# Sheet1.net
KiCad netlist of a schematic drawn in Altium Designer
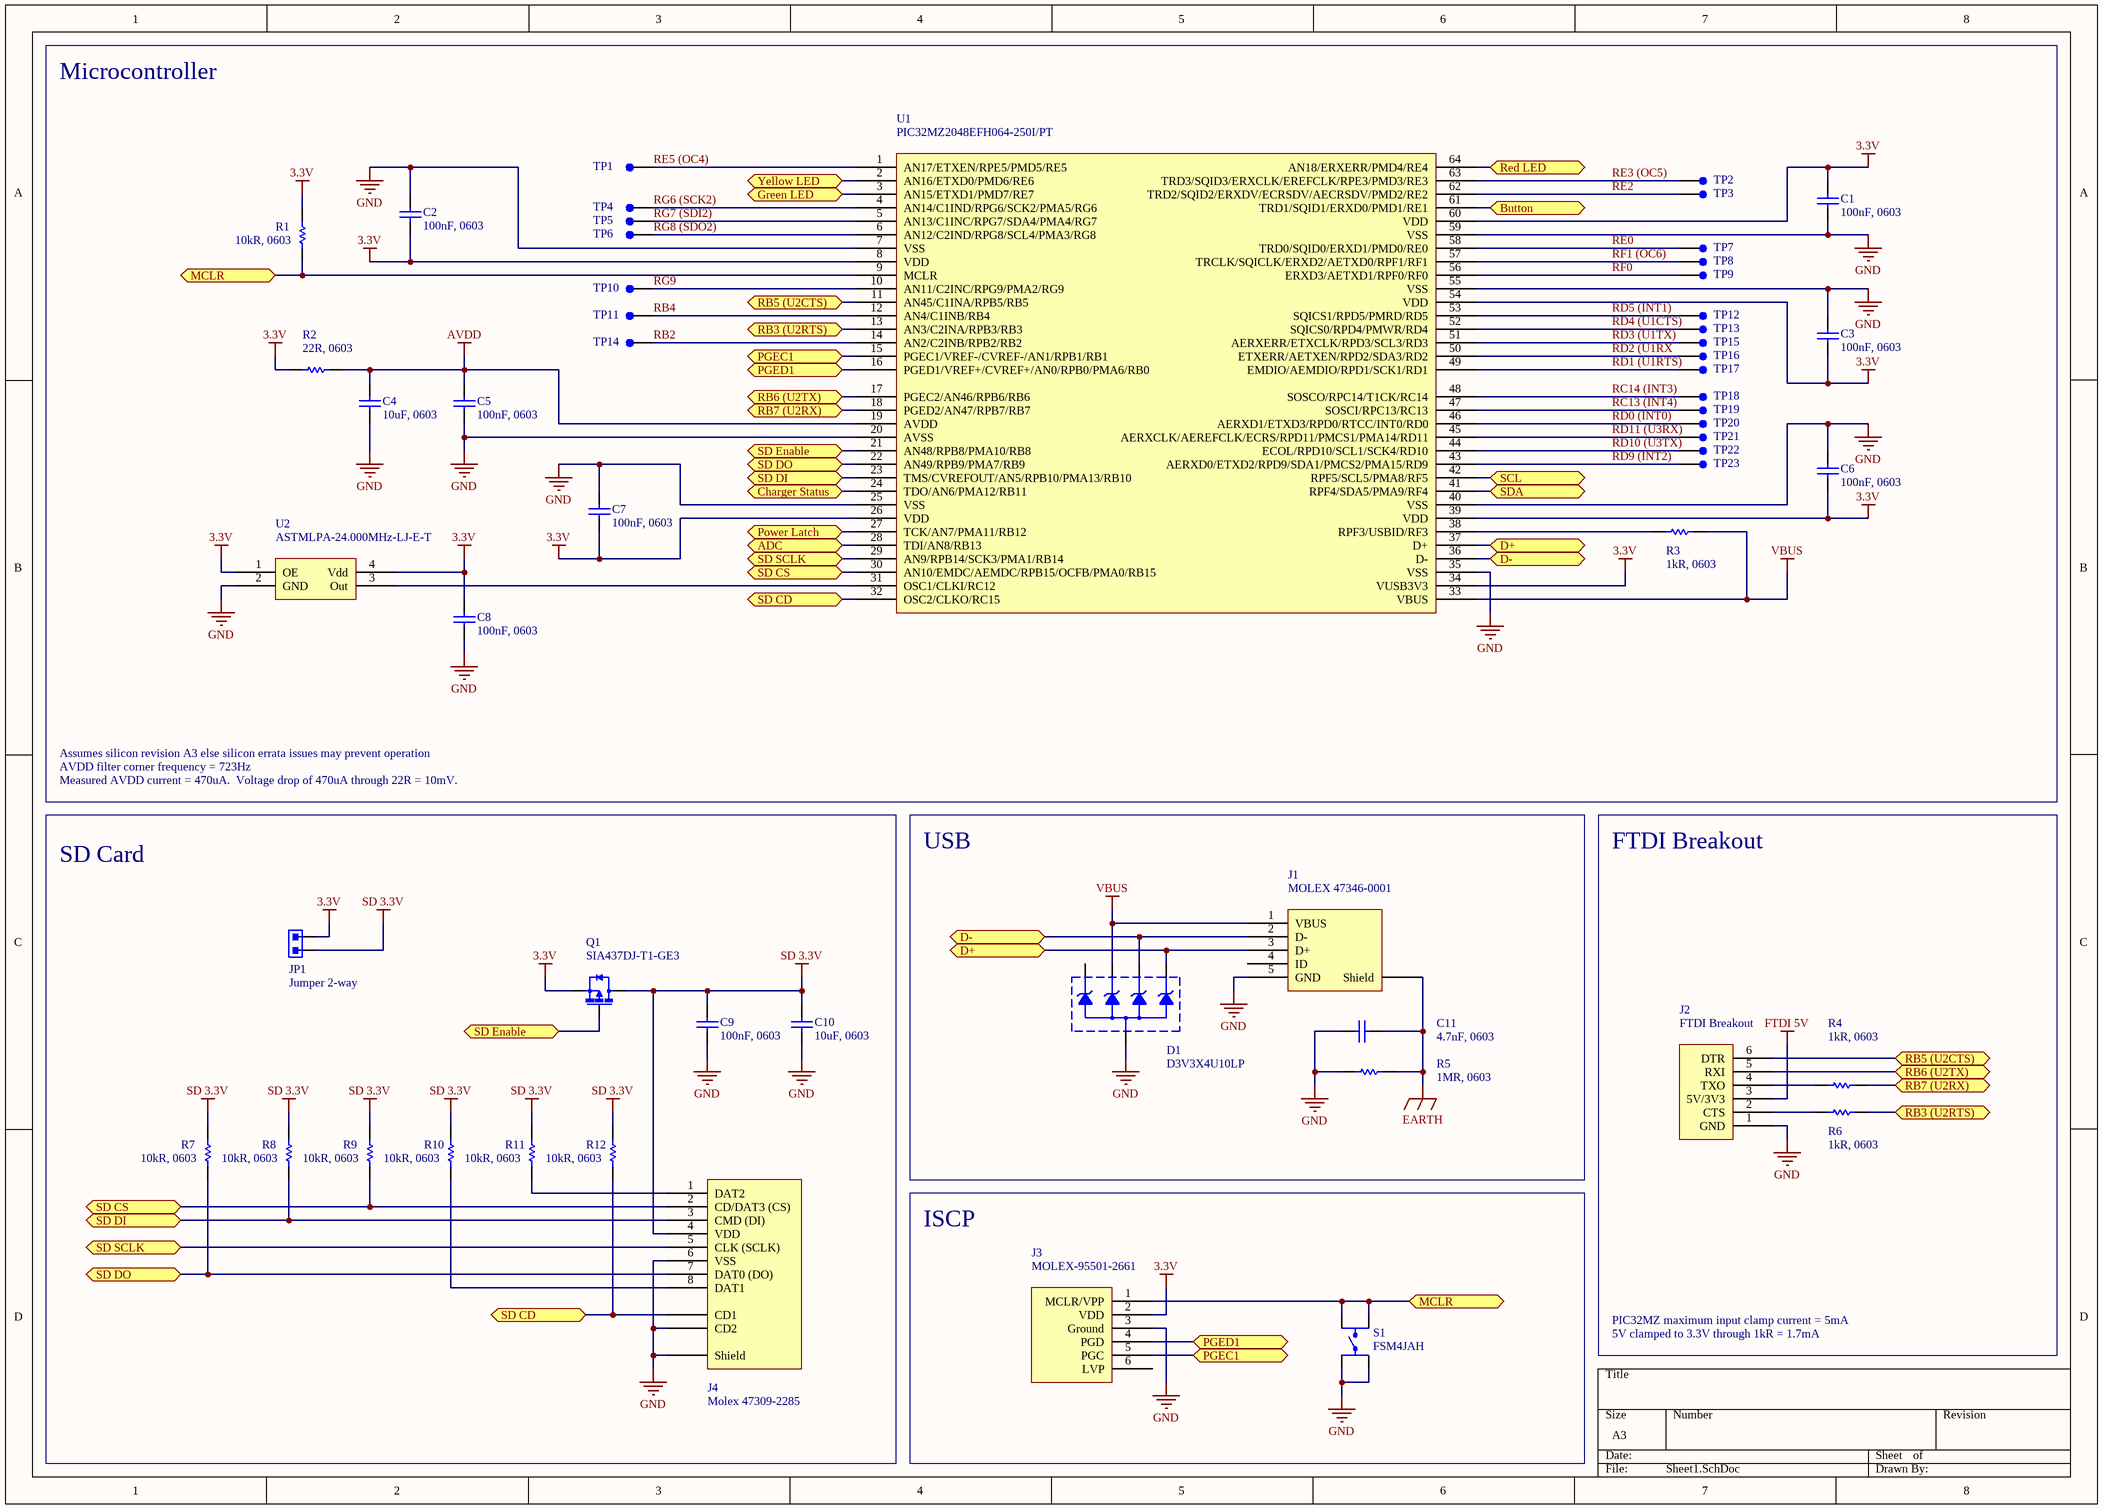
[diagram p0: Sheet1.SchDoc]

(export (version "E")
  (design (tool "Eeschema 10.0.6"))
  (components
    (comp (ref "C1")
      (value "100nF, 0603")
      (footprint "Capacitor 0603")
      (libsource (lib "x-io") (part "Capacitor"))
    )
    (comp (ref "C2")
      (value "100nF, 0603")
      (footprint "Capacitor 0603")
      (libsource (lib "x-io") (part "Capacitor"))
    )
    (comp (ref "C3")
      (value "100nF, 0603")
      (footprint "Capacitor 0603")
      (libsource (lib "x-io") (part "Capacitor"))
    )
    (comp (ref "C4")
      (value "10uF, 0603")
      (footprint "Capacitor 0603")
      (libsource (lib "x-io") (part "Capacitor"))
    )
    (comp (ref "C5")
      (value "100nF, 0603")
      (footprint "Capacitor 0603")
      (libsource (lib "x-io") (part "Capacitor"))
    )
    (comp (ref "C6")
      (value "100nF, 0603")
      (footprint "Capacitor 0603")
      (libsource (lib "x-io") (part "Capacitor"))
    )
    (comp (ref "C7")
      (value "100nF, 0603")
      (footprint "Capacitor 0603")
      (libsource (lib "x-io") (part "Capacitor"))
    )
    (comp (ref "C8")
      (value "100nF, 0603")
      (footprint "Capacitor 0603")
      (libsource (lib "x-io") (part "Capacitor"))
    )
    (comp (ref "C9")
      (value "100nF, 0603")
      (footprint "Capacitor 0603")
      (libsource (lib "x-io") (part "Capacitor"))
    )
    (comp (ref "C10")
      (value "10uF, 0603")
      (footprint "Capacitor 0603")
      (libsource (lib "x-io") (part "Capacitor"))
    )
    (comp (ref "C11")
      (value "4.7nF, 0603")
      (footprint "Capacitor 0603")
      (libsource (lib "x-io") (part "Capacitor"))
    )
    (comp (ref "D1")
      (value "D3V3X4U10LP")
      (footprint "D3V3X4U10LP")
      (libsource (lib "x-io") (part "D3V3X4U10LP"))
    )
    (comp (ref "J1")
      (value "MOLEX 47346-0001")
      (footprint "Molex 47346-0001")
      (libsource (lib "x-io") (part "USB Socket"))
    )
    (comp (ref "J2")
      (value "FTDI Breakout")
      (footprint "FTDI Breakout")
      (libsource (lib "x-io") (part "FTDI Breakout"))
    )
    (comp (ref "J3")
      (value "MOLEX-95501-2661")
      (footprint "MOLEX-95501-2661")
      (libsource (lib "x-io") (part "MPLAB ICD 3"))
    )
    (comp (ref "J4")
      (value "Molex 47309-2285")
      (footprint "Molex 47309-2285")
      (libsource (lib "x-io") (part "Molex 47309-2285"))
    )
    (comp (ref "JP1")
      (value "Jumper 2-way")
      (footprint "Jumper 2-way")
      (libsource (lib "x-io") (part "Jumper 2-way"))
    )
    (comp (ref "Q1")
      (value "SIA437DJ-T1-GE3")
      (footprint "SIA437DJ-T1-GE3")
      (libsource (lib "x-io") (part "MOSFET P-Channel"))
    )
    (comp (ref "R1")
      (value "10kR, 0603")
      (footprint "Resistor 0603")
      (libsource (lib "x-io") (part "Resistor"))
    )
    (comp (ref "R2")
      (value "22R, 0603")
      (footprint "Resistor 0603")
      (libsource (lib "x-io") (part "Resistor"))
    )
    (comp (ref "R3")
      (value "1kR, 0603")
      (footprint "Resistor 0603")
      (libsource (lib "x-io") (part "Resistor"))
    )
    (comp (ref "R4")
      (value "1kR, 0603")
      (footprint "Resistor 0603")
      (libsource (lib "x-io") (part "Resistor"))
    )
    (comp (ref "R5")
      (value "1MR, 0603")
      (footprint "Resistor 0603")
      (libsource (lib "x-io") (part "Resistor"))
    )
    (comp (ref "R6")
      (value "1kR, 0603")
      (footprint "Resistor 0603")
      (libsource (lib "x-io") (part "Resistor"))
    )
    (comp (ref "R7")
      (value "10kR, 0603")
      (footprint "Resistor 0603")
      (libsource (lib "x-io") (part "Resistor"))
    )
    (comp (ref "R8")
      (value "10kR, 0603")
      (footprint "Resistor 0603")
      (libsource (lib "x-io") (part "Resistor"))
    )
    (comp (ref "R9")
      (value "10kR, 0603")
      (footprint "Resistor 0603")
      (libsource (lib "x-io") (part "Resistor"))
    )
    (comp (ref "R10")
      (value "10kR, 0603")
      (footprint "Resistor 0603")
      (libsource (lib "x-io") (part "Resistor"))
    )
    (comp (ref "R11")
      (value "10kR, 0603")
      (footprint "Resistor 0603")
      (libsource (lib "x-io") (part "Resistor"))
    )
    (comp (ref "R12")
      (value "10kR, 0603")
      (footprint "Resistor 0603")
      (libsource (lib "x-io") (part "Resistor"))
    )
    (comp (ref "S1") (value "FSM4JAH") (footprint "FSM4JHX") (libsource (lib "x-io") (part "Tactile Switch")))
    (comp (ref "TP1")
      (value "Test Point")
      (footprint "Test Point 1.5mm")
      (libsource (lib "x-io") (part "Test Point"))
    )
    (comp (ref "TP2")
      (value "Test Point")
      (footprint "Test Point 1.5mm")
      (libsource (lib "x-io") (part "Test Point"))
    )
    (comp (ref "TP3")
      (value "Test Point")
      (footprint "Test Point 1.5mm")
      (libsource (lib "x-io") (part "Test Point"))
    )
    (comp (ref "TP4")
      (value "Test Point")
      (footprint "Test Point 1.5mm")
      (libsource (lib "x-io") (part "Test Point"))
    )
    (comp (ref "TP5")
      (value "Test Point")
      (footprint "Test Point 1.5mm")
      (libsource (lib "x-io") (part "Test Point"))
    )
    (comp (ref "TP6")
      (value "Test Point")
      (footprint "Test Point 1.5mm")
      (libsource (lib "x-io") (part "Test Point"))
    )
    (comp (ref "TP7")
      (value "Test Point")
      (footprint "Test Point 1.5mm")
      (libsource (lib "x-io") (part "Test Point"))
    )
    (comp (ref "TP8")
      (value "Test Point")
      (footprint "Test Point 1.5mm")
      (libsource (lib "x-io") (part "Test Point"))
    )
    (comp (ref "TP9")
      (value "Test Point")
      (footprint "Test Point 1.5mm")
      (libsource (lib "x-io") (part "Test Point"))
    )
    (comp (ref "TP10")
      (value "Test Point")
      (footprint "Test Point 1.5mm")
      (libsource (lib "x-io") (part "Test Point"))
    )
    (comp (ref "TP11")
      (value "Test Point")
      (footprint "Test Point 1.5mm")
      (libsource (lib "x-io") (part "Test Point"))
    )
    (comp (ref "TP12")
      (value "Test Point")
      (footprint "Test Point 1.5mm")
      (libsource (lib "x-io") (part "Test Point"))
    )
    (comp (ref "TP13")
      (value "Test Point")
      (footprint "Test Point 1.5mm")
      (libsource (lib "x-io") (part "Test Point"))
    )
    (comp (ref "TP14")
      (value "Test Point")
      (footprint "Test Point 1.5mm")
      (libsource (lib "x-io") (part "Test Point"))
    )
    (comp (ref "TP15")
      (value "Test Point")
      (footprint "Test Point 1.5mm")
      (libsource (lib "x-io") (part "Test Point"))
    )
    (comp (ref "TP16")
      (value "Test Point")
      (footprint "Test Point 1.5mm")
      (libsource (lib "x-io") (part "Test Point"))
    )
    (comp (ref "TP17")
      (value "Test Point")
      (footprint "Test Point 1.5mm")
      (libsource (lib "x-io") (part "Test Point"))
    )
    (comp (ref "TP18")
      (value "Test Point")
      (footprint "Test Point 1.5mm")
      (libsource (lib "x-io") (part "Test Point"))
    )
    (comp (ref "TP19")
      (value "Test Point")
      (footprint "Test Point 1.5mm")
      (libsource (lib "x-io") (part "Test Point"))
    )
    (comp (ref "TP20")
      (value "Test Point")
      (footprint "Test Point 1.5mm")
      (libsource (lib "x-io") (part "Test Point"))
    )
    (comp (ref "TP21")
      (value "Test Point")
      (footprint "Test Point 1.5mm")
      (libsource (lib "x-io") (part "Test Point"))
    )
    (comp (ref "TP22")
      (value "Test Point")
      (footprint "Test Point 1.5mm")
      (libsource (lib "x-io") (part "Test Point"))
    )
    (comp (ref "TP23")
      (value "Test Point")
      (footprint "Test Point 1.5mm")
      (libsource (lib "x-io") (part "Test Point"))
    )
    (comp (ref "U1")
      (value "PIC32MZ2048EFH064-250I/PT")
      (footprint "TQFP-64")
      (libsource (lib "x-io") (part "PIC32MZ2048EFH064"))
    )
    (comp (ref "U2")
      (value "ASTMLPA-24.000MHz-LJ-E-T")
      (footprint "ASTMLPA")
      (libsource (lib "x-io") (part "ASTMLPA-24.000MHz-LJ-E-T"))
    )
  )
  (nets
    (net (code "1") (name "/ADC") (class "Default")
      (node (ref "U1") (pin "28") (pinfunction "TDI/AN8/RB13_28") (pintype "passive"))
    )
    (net (code "2") (name "/Button") (class "Default")
      (node (ref "U1") (pin "61") (pinfunction "TRD1/SQID1/ERXD0/PMD1/RE1_61") (pintype "passive"))
    )
    (net (code "3") (name "/Charger Status") (class "Default")
      (node (ref "U1") (pin "24") (pinfunction "TDO/AN6/PMA12/RB11_24") (pintype "passive"))
    )
    (net (code "4") (name "/D+") (class "Default")
      (node (ref "D1") (pin "K4") (pinfunction "K4_K4") (pintype "passive"))
      (node (ref "J1") (pin "3") (pinfunction "D+_3") (pintype "passive"))
      (node (ref "U1") (pin "37") (pinfunction "D+_37") (pintype "passive"))
    )
    (net (code "5") (name "/D-") (class "Default")
      (node (ref "D1") (pin "K3") (pinfunction "K3_K3") (pintype "passive"))
      (node (ref "J1") (pin "2") (pinfunction "D-_2") (pintype "passive"))
      (node (ref "U1") (pin "36") (pinfunction "D-_36") (pintype "passive"))
    )
    (net (code "6") (name "/Green LED") (class "Default")
      (node (ref "U1") (pin "3") (pinfunction "AN15/ETXD1/PMD7/RE7_3") (pintype "passive"))
    )
    (net (code "7") (name "/MCLR") (class "Default")
      (node (ref "J3") (pin "1") (pinfunction "MCLR/VPP_1") (pintype "passive"))
      (node (ref "R1") (pin "1") (pinfunction "1_1") (pintype "passive"))
      (node (ref "S1") (pin "3") (pinfunction "3_3") (pintype "passive"))
      (node (ref "S1") (pin "4") (pinfunction "4_4") (pintype "passive"))
      (node (ref "U1") (pin "9") (pinfunction "MCLR_9") (pintype "passive"))
    )
    (net (code "8") (name "/PGEC1") (class "Default")
      (node (ref "J3") (pin "5") (pinfunction "PGC_5") (pintype "passive"))
      (node (ref "U1") (pin "15") (pinfunction "PGEC1/VREF-/CVREF-/AN1/RPB1/RB1_15") (pintype "passive"))
    )
    (net (code "9") (name "/PGED1") (class "Default")
      (node (ref "J3") (pin "4") (pinfunction "PGD_4") (pintype "passive"))
      (node (ref "U1") (pin "16") (pinfunction "PGED1/VREF+/CVREF+/AN0/RPB0/PMA6/RB0_16") (pintype "passive"))
    )
    (net (code "10") (name "/Power Latch") (class "Default")
      (node (ref "U1") (pin "27") (pinfunction "TCK/AN7/PMA11/RB12_27") (pintype "passive"))
    )
    (net (code "11") (name "/RB2") (class "Default")
      (node (ref "TP14") (pin "1") (pinfunction "1_1") (pintype "passive"))
      (node (ref "U1") (pin "14") (pinfunction "AN2/C2INB/RPB2/RB2_14") (pintype "passive"))
    )
    (net (code "12") (name "/RB3 (U2RTS)") (class "Default")
      (node (ref "R6") (pin "1") (pinfunction "1_1") (pintype "passive"))
      (node (ref "U1") (pin "13") (pinfunction "AN3/C2INA/RPB3/RB3_13") (pintype "passive"))
    )
    (net (code "13") (name "/RB4") (class "Default")
      (node (ref "TP11") (pin "1") (pinfunction "1_1") (pintype "passive"))
      (node (ref "U1") (pin "12") (pinfunction "AN4/C1INB/RB4_12") (pintype "passive"))
    )
    (net (code "14") (name "/RB5 (U2CTS)") (class "Default")
      (node (ref "J2") (pin "6") (pinfunction "DTR_6") (pintype "passive"))
      (node (ref "U1") (pin "11") (pinfunction "AN45/C1INA/RPB5/RB5_11") (pintype "passive"))
    )
    (net (code "15") (name "/RB6 (U2TX)") (class "Default")
      (node (ref "J2") (pin "5") (pinfunction "RXI_5") (pintype "passive"))
      (node (ref "U1") (pin "17") (pinfunction "PGEC2/AN46/RPB6/RB6_17") (pintype "passive"))
    )
    (net (code "16") (name "/RB7 (U2RX)") (class "Default")
      (node (ref "R4") (pin "1") (pinfunction "1_1") (pintype "passive"))
      (node (ref "U1") (pin "18") (pinfunction "PGED2/AN47/RPB7/RB7_18") (pintype "passive"))
    )
    (net (code "17") (name "/RC13 (INT4)") (class "Default")
      (node (ref "TP19") (pin "1") (pinfunction "1_1") (pintype "passive"))
      (node (ref "U1") (pin "47") (pinfunction "SOSCI/RPC13/RC13_47") (pintype "passive"))
    )
    (net (code "18") (name "/RC14 (INT3)") (class "Default")
      (node (ref "TP18") (pin "1") (pinfunction "1_1") (pintype "passive"))
      (node (ref "U1") (pin "48") (pinfunction "SOSCO/RPC14/T1CK/RC14_48") (pintype "passive"))
    )
    (net (code "19") (name "/RD0 (INT0)") (class "Default")
      (node (ref "TP20") (pin "1") (pinfunction "1_1") (pintype "passive"))
      (node (ref "U1") (pin "46") (pinfunction "AERXD1/ETXD3/RPD0/RTCC/INT0/RD0_46") (pintype "passive"))
    )
    (net (code "20") (name "/RD1 (U1RTS)") (class "Default")
      (node (ref "TP17") (pin "1") (pinfunction "1_1") (pintype "passive"))
      (node (ref "U1") (pin "49") (pinfunction "EMDIO/AEMDIO/RPD1/SCK1/RD1_49") (pintype "passive"))
    )
    (net (code "21") (name "/RD2 (U1RX") (class "Default")
      (node (ref "TP16") (pin "1") (pinfunction "1_1") (pintype "passive"))
      (node (ref "U1") (pin "50") (pinfunction "ETXERR/AETXEN/RPD2/SDA3/RD2_50") (pintype "passive"))
    )
    (net (code "22") (name "/RD3 (U1TX)") (class "Default")
      (node (ref "TP15") (pin "1") (pinfunction "1_1") (pintype "passive"))
      (node (ref "U1") (pin "51") (pinfunction "AERXERR/ETXCLK/RPD3/SCL3/RD3_51") (pintype "passive"))
    )
    (net (code "23") (name "/RD4 (U1CTS)") (class "Default")
      (node (ref "TP13") (pin "1") (pinfunction "1_1") (pintype "passive"))
      (node (ref "U1") (pin "52") (pinfunction "SQICS0/RPD4/PMWR/RD4_52") (pintype "passive"))
    )
    (net (code "24") (name "/RD5 (INT1)") (class "Default")
      (node (ref "TP12") (pin "1") (pinfunction "1_1") (pintype "passive"))
      (node (ref "U1") (pin "53") (pinfunction "SQICS1/RPD5/PMRD/RD5_53") (pintype "passive"))
    )
    (net (code "25") (name "/RD9 (INT2)") (class "Default")
      (node (ref "TP23") (pin "1") (pinfunction "1_1") (pintype "passive"))
      (node (ref "U1") (pin "43") (pinfunction "AERXD0/ETXD2/RPD9/SDA1/PMCS2/PMA15/RD9_43") (pintype "passive"))
    )
    (net (code "26") (name "/RD10 (U3TX)") (class "Default")
      (node (ref "TP22") (pin "1") (pinfunction "1_1") (pintype "passive"))
      (node (ref "U1") (pin "44") (pinfunction "ECOL/RPD10/SCL1/SCK4/RD10_44") (pintype "passive"))
    )
    (net (code "27") (name "/RD11 (U3RX)") (class "Default")
      (node (ref "TP21") (pin "1") (pinfunction "1_1") (pintype "passive"))
      (node (ref "U1") (pin "45") (pinfunction "AERXCLK/AEREFCLK/ECRS/RPD11/PMCS1/PMA14/RD11_45") (pintype "passive"))
    )
    (net (code "28") (name "/RE0") (class "Default")
      (node (ref "TP7") (pin "1") (pinfunction "1_1") (pintype "passive"))
      (node (ref "U1") (pin "58") (pinfunction "TRD0/SQID0/ERXD1/PMD0/RE0_58") (pintype "passive"))
    )
    (net (code "29") (name "/RE2") (class "Default")
      (node (ref "TP3") (pin "1") (pinfunction "1_1") (pintype "passive"))
      (node (ref "U1") (pin "62") (pinfunction "TRD2/SQID2/ERXDV/ECRSDV/AECRSDV/PMD2/RE2_62") (pintype "passive"))
    )
    (net (code "30") (name "/RE3 (OC5)") (class "Default")
      (node (ref "TP2") (pin "1") (pinfunction "1_1") (pintype "passive"))
      (node (ref "U1") (pin "63") (pinfunction "TRD3/SQID3/ERXCLK/EREFCLK/RPE3/PMD3/RE3_63") (pintype "passive"))
    )
    (net (code "31") (name "/RE5 (OC4)") (class "Default")
      (node (ref "TP1") (pin "1") (pinfunction "1_1") (pintype "passive"))
      (node (ref "U1") (pin "1") (pinfunction "AN17/ETXEN/RPE5/PMD5/RE5_1") (pintype "passive"))
    )
    (net (code "32") (name "/RF0") (class "Default")
      (node (ref "TP9") (pin "1") (pinfunction "1_1") (pintype "passive"))
      (node (ref "U1") (pin "56") (pinfunction "ERXD3/AETXD1/RPF0/RF0_56") (pintype "passive"))
    )
    (net (code "33") (name "/RF1 (OC6)") (class "Default")
      (node (ref "TP8") (pin "1") (pinfunction "1_1") (pintype "passive"))
      (node (ref "U1") (pin "57") (pinfunction "TRCLK/SQICLK/ERXD2/AETXD0/RPF1/RF1_57") (pintype "passive"))
    )
    (net (code "34") (name "/RG6 (SCK2)") (class "Default")
      (node (ref "TP4") (pin "1") (pinfunction "1_1") (pintype "passive"))
      (node (ref "U1") (pin "4") (pinfunction "AN14/C1IND/RPG6/SCK2/PMA5/RG6_4") (pintype "passive"))
    )
    (net (code "35") (name "/RG7 (SDI2)") (class "Default")
      (node (ref "TP5") (pin "1") (pinfunction "1_1") (pintype "passive"))
      (node (ref "U1") (pin "5") (pinfunction "AN13/C1INC/RPG7/SDA4/PMA4/RG7_5") (pintype "passive"))
    )
    (net (code "36") (name "/RG8 (SDO2)") (class "Default")
      (node (ref "TP6") (pin "1") (pinfunction "1_1") (pintype "passive"))
      (node (ref "U1") (pin "6") (pinfunction "AN12/C2IND/RPG8/SCL4/PMA3/RG8_6") (pintype "passive"))
    )
    (net (code "37") (name "/RG9") (class "Default")
      (node (ref "TP10") (pin "1") (pinfunction "1_1") (pintype "passive"))
      (node (ref "U1") (pin "10") (pinfunction "AN11/C2INC/RPG9/PMA2/RG9_10") (pintype "passive"))
    )
    (net (code "38") (name "/Red LED") (class "Default")
      (node (ref "U1") (pin "64") (pinfunction "AN18/ERXERR/PMD4/RE4_64") (pintype "passive"))
    )
    (net (code "39") (name "/SCL") (class "Default")
      (node (ref "U1") (pin "42") (pinfunction "RPF5/SCL5/PMA8/RF5_42") (pintype "passive"))
    )
    (net (code "40") (name "/SD CD") (class "Default")
      (node (ref "J4") (pin "CD1") (pinfunction "CD1_CD1") (pintype "passive"))
      (node (ref "R12") (pin "1") (pinfunction "1_1") (pintype "passive"))
      (node (ref "U1") (pin "32") (pinfunction "OSC2/CLKO/RC15_32") (pintype "passive"))
    )
    (net (code "41") (name "/SD CS") (class "Default")
      (node (ref "J4") (pin "2") (pinfunction "CD/DAT3_(CS)_2") (pintype "passive"))
      (node (ref "R9") (pin "1") (pinfunction "1_1") (pintype "passive"))
      (node (ref "U1") (pin "30") (pinfunction "AN10/EMDC/AEMDC/RPB15/OCFB/PMA0/RB15_30") (pintype "passive"))
    )
    (net (code "42") (name "/SD DI") (class "Default")
      (node (ref "J4") (pin "3") (pinfunction "CMD_(DI)_3") (pintype "passive"))
      (node (ref "R8") (pin "1") (pinfunction "1_1") (pintype "passive"))
      (node (ref "U1") (pin "23") (pinfunction "TMS/CVREFOUT/AN5/RPB10/PMA13/RB10_23") (pintype "passive"))
    )
    (net (code "43") (name "/SD DO") (class "Default")
      (node (ref "J4") (pin "7") (pinfunction "DAT0_(DO)_7") (pintype "passive"))
      (node (ref "R7") (pin "1") (pinfunction "1_1") (pintype "passive"))
      (node (ref "U1") (pin "22") (pinfunction "AN49/RPB9/PMA7/RB9_22") (pintype "passive"))
    )
    (net (code "44") (name "/SD Enable") (class "Default")
      (node (ref "Q1") (pin "G") (pinfunction "G_G") (pintype "passive"))
      (node (ref "U1") (pin "21") (pinfunction "AN48/RPB8/PMA10/RB8_21") (pintype "passive"))
    )
    (net (code "45") (name "/SD SCLK") (class "Default")
      (node (ref "J4") (pin "5") (pinfunction "CLK_(SCLK)_5") (pintype "passive"))
      (node (ref "U1") (pin "29") (pinfunction "AN9/RPB14/SCK3/PMA1/RB14_29") (pintype "passive"))
    )
    (net (code "46") (name "/SDA") (class "Default")
      (node (ref "U1") (pin "41") (pinfunction "RPF4/SDA5/PMA9/RF4_41") (pintype "passive"))
    )
    (net (code "47") (name "/Yellow LED") (class "Default")
      (node (ref "U1") (pin "2") (pinfunction "AN16/ETXD0/PMD6/RE6_2") (pintype "passive"))
    )
    (net (code "48") (name "3.3V") (class "Default")
      (node (ref "C1") (pin "1") (pinfunction "1_1") (pintype "passive"))
      (node (ref "C2") (pin "1") (pinfunction "1_1") (pintype "passive"))
      (node (ref "C3") (pin "2") (pinfunction "2_2") (pintype "passive"))
      (node (ref "C6") (pin "2") (pinfunction "2_2") (pintype "passive"))
      (node (ref "C7") (pin "1") (pinfunction "1_1") (pintype "passive"))
      (node (ref "C8") (pin "2") (pinfunction "2_2") (pintype "passive"))
      (node (ref "J3") (pin "2") (pinfunction "VDD_2") (pintype "passive"))
      (node (ref "JP1") (pin "1") (pinfunction "1_1") (pintype "passive"))
      (node (ref "Q1") (pin "S") (pinfunction "S_S") (pintype "passive"))
      (node (ref "R1") (pin "2") (pinfunction "2_2") (pintype "passive"))
      (node (ref "R2") (pin "2") (pinfunction "2_2") (pintype "passive"))
      (node (ref "U1") (pin "26") (pinfunction "VDD_26") (pintype "passive"))
      (node (ref "U1") (pin "34") (pinfunction "VUSB3V3_34") (pintype "passive"))
      (node (ref "U1") (pin "39") (pinfunction "VDD_39") (pintype "passive"))
      (node (ref "U1") (pin "54") (pinfunction "VDD_54") (pintype "passive"))
      (node (ref "U1") (pin "60") (pinfunction "VDD_60") (pintype "passive"))
      (node (ref "U1") (pin "8") (pinfunction "VDD_8") (pintype "passive"))
      (node (ref "U2") (pin "1") (pinfunction "OE_1") (pintype "passive"))
      (node (ref "U2") (pin "4") (pinfunction "Vdd_4") (pintype "passive"))
    )
    (net (code "49") (name "AVDD") (class "Default")
      (node (ref "C4") (pin "2") (pinfunction "2_2") (pintype "passive"))
      (node (ref "C5") (pin "2") (pinfunction "2_2") (pintype "passive"))
      (node (ref "R2") (pin "1") (pinfunction "1_1") (pintype "passive"))
      (node (ref "U1") (pin "19") (pinfunction "AVDD_19") (pintype "passive"))
    )
    (net (code "50") (name "EARTH") (class "Default")
      (node (ref "C11") (pin "2") (pinfunction "2_2") (pintype "passive"))
      (node (ref "J1") (pin "Shield") (pinfunction "Shield_Shield") (pintype "passive"))
      (node (ref "R5") (pin "2") (pinfunction "2_2") (pintype "passive"))
    )
    (net (code "51") (name "FTDI 5V") (class "Default")
      (node (ref "J2") (pin "3") (pinfunction "5V/3V3_3") (pintype "passive"))
    )
    (net (code "52") (name "GND") (class "Default")
      (node (ref "C1") (pin "2") (pinfunction "2_2") (pintype "passive"))
      (node (ref "C10") (pin "1") (pinfunction "1_1") (pintype "passive"))
      (node (ref "C11") (pin "1") (pinfunction "1_1") (pintype "passive"))
      (node (ref "C2") (pin "2") (pinfunction "2_2") (pintype "passive"))
      (node (ref "C3") (pin "1") (pinfunction "1_1") (pintype "passive"))
      (node (ref "C4") (pin "1") (pinfunction "1_1") (pintype "passive"))
      (node (ref "C5") (pin "1") (pinfunction "1_1") (pintype "passive"))
      (node (ref "C6") (pin "1") (pinfunction "1_1") (pintype "passive"))
      (node (ref "C7") (pin "2") (pinfunction "2_2") (pintype "passive"))
      (node (ref "C8") (pin "1") (pinfunction "1_1") (pintype "passive"))
      (node (ref "C9") (pin "1") (pinfunction "1_1") (pintype "passive"))
      (node (ref "D1") (pin "A") (pinfunction "A_A") (pintype "passive"))
      (node (ref "J1") (pin "5") (pinfunction "GND_5") (pintype "passive"))
      (node (ref "J2") (pin "1") (pinfunction "GND_1") (pintype "passive"))
      (node (ref "J3") (pin "3") (pinfunction "Ground_3") (pintype "passive"))
      (node (ref "J4") (pin "6") (pinfunction "VSS_6") (pintype "passive"))
      (node (ref "J4") (pin "CD2") (pinfunction "CD2_CD2") (pintype "passive"))
      (node (ref "J4") (pin "Shield") (pinfunction "Shield_Shield") (pintype "passive"))
      (node (ref "R5") (pin "1") (pinfunction "1_1") (pintype "passive"))
      (node (ref "S1") (pin "1") (pinfunction "1_1") (pintype "passive"))
      (node (ref "S1") (pin "2") (pinfunction "2_2") (pintype "passive"))
      (node (ref "U1") (pin "20") (pinfunction "AVSS_20") (pintype "passive"))
      (node (ref "U1") (pin "25") (pinfunction "VSS_25") (pintype "passive"))
      (node (ref "U1") (pin "35") (pinfunction "VSS_35") (pintype "passive"))
      (node (ref "U1") (pin "40") (pinfunction "VSS_40") (pintype "passive"))
      (node (ref "U1") (pin "55") (pinfunction "VSS_55") (pintype "passive"))
      (node (ref "U1") (pin "59") (pinfunction "VSS_59") (pintype "passive"))
      (node (ref "U1") (pin "7") (pinfunction "VSS_7") (pintype "passive"))
      (node (ref "U2") (pin "2") (pinfunction "GND_2") (pintype "passive"))
    )
    (net (code "53") (name "Net-(J2-CTS)") (class "Default")
      (node (ref "J2") (pin "2") (pinfunction "CTS_2") (pintype "passive"))
      (node (ref "R6") (pin "2") (pinfunction "2_2") (pintype "passive"))
    )
    (net (code "54") (name "Net-(J2-TXO)") (class "Default")
      (node (ref "J2") (pin "4") (pinfunction "TXO_4") (pintype "passive"))
      (node (ref "R4") (pin "2") (pinfunction "2_2") (pintype "passive"))
    )
    (net (code "55") (name "Net-(J4-DAT1)") (class "Default")
      (node (ref "J4") (pin "8") (pinfunction "DAT1_8") (pintype "passive"))
      (node (ref "R10") (pin "1") (pinfunction "1_1") (pintype "passive"))
    )
    (net (code "56") (name "Net-(J4-DAT2)") (class "Default")
      (node (ref "J4") (pin "1") (pinfunction "DAT2_1") (pintype "passive"))
      (node (ref "R11") (pin "1") (pinfunction "1_1") (pintype "passive"))
    )
    (net (code "57") (name "Net-(U1-OSC1{slash}CLKI{slash}RC12)") (class "Default")
      (node (ref "U1") (pin "31") (pinfunction "OSC1/CLKI/RC12_31") (pintype "passive"))
      (node (ref "U2") (pin "3") (pinfunction "Out_3") (pintype "passive"))
    )
    (net (code "58") (name "Net-(U1-RPF3{slash}USBID{slash}RF3)") (class "Default")
      (node (ref "R3") (pin "2") (pinfunction "2_2") (pintype "passive"))
      (node (ref "U1") (pin "38") (pinfunction "RPF3/USBID/RF3_38") (pintype "passive"))
    )
    (net (code "59") (name "SD 3.3V") (class "Default")
      (node (ref "C10") (pin "2") (pinfunction "2_2") (pintype "passive"))
      (node (ref "C9") (pin "2") (pinfunction "2_2") (pintype "passive"))
      (node (ref "J4") (pin "4") (pinfunction "VDD_4") (pintype "passive"))
      (node (ref "JP1") (pin "2") (pinfunction "2_2") (pintype "passive"))
      (node (ref "Q1") (pin "D") (pinfunction "D_D") (pintype "passive"))
      (node (ref "R10") (pin "2") (pinfunction "2_2") (pintype "passive"))
      (node (ref "R11") (pin "2") (pinfunction "2_2") (pintype "passive"))
      (node (ref "R12") (pin "2") (pinfunction "2_2") (pintype "passive"))
      (node (ref "R7") (pin "2") (pinfunction "2_2") (pintype "passive"))
      (node (ref "R8") (pin "2") (pinfunction "2_2") (pintype "passive"))
      (node (ref "R9") (pin "2") (pinfunction "2_2") (pintype "passive"))
    )
    (net (code "60") (name "VBUS") (class "Default")
      (node (ref "D1") (pin "K2") (pinfunction "K2_K2") (pintype "passive"))
      (node (ref "J1") (pin "1") (pinfunction "VBUS_1") (pintype "passive"))
      (node (ref "R3") (pin "1") (pinfunction "1_1") (pintype "passive"))
      (node (ref "U1") (pin "33") (pinfunction "VBUS_33") (pintype "passive"))
    )
    (net (code "61") (name "unconnected-(D1-PadK1)") (class "Default")
      (node (ref "D1") (pin "K1") (pinfunction "K1_K1") (pintype "passive"))
    )
    (net (code "62") (name "unconnected-(J1-ID-Pad4)") (class "Default")
      (node (ref "J1") (pin "4") (pinfunction "ID_4") (pintype "passive"))
    )
    (net (code "63") (name "unconnected-(J3-LVP-Pad6)") (class "Default")
      (node (ref "J3") (pin "6") (pinfunction "LVP_6") (pintype "passive"))
    )
  )
)
